# c64-stripefixvidbuf_v0_21-maxIC.net
KiCad netlist of a schematic drawn in EAGLE
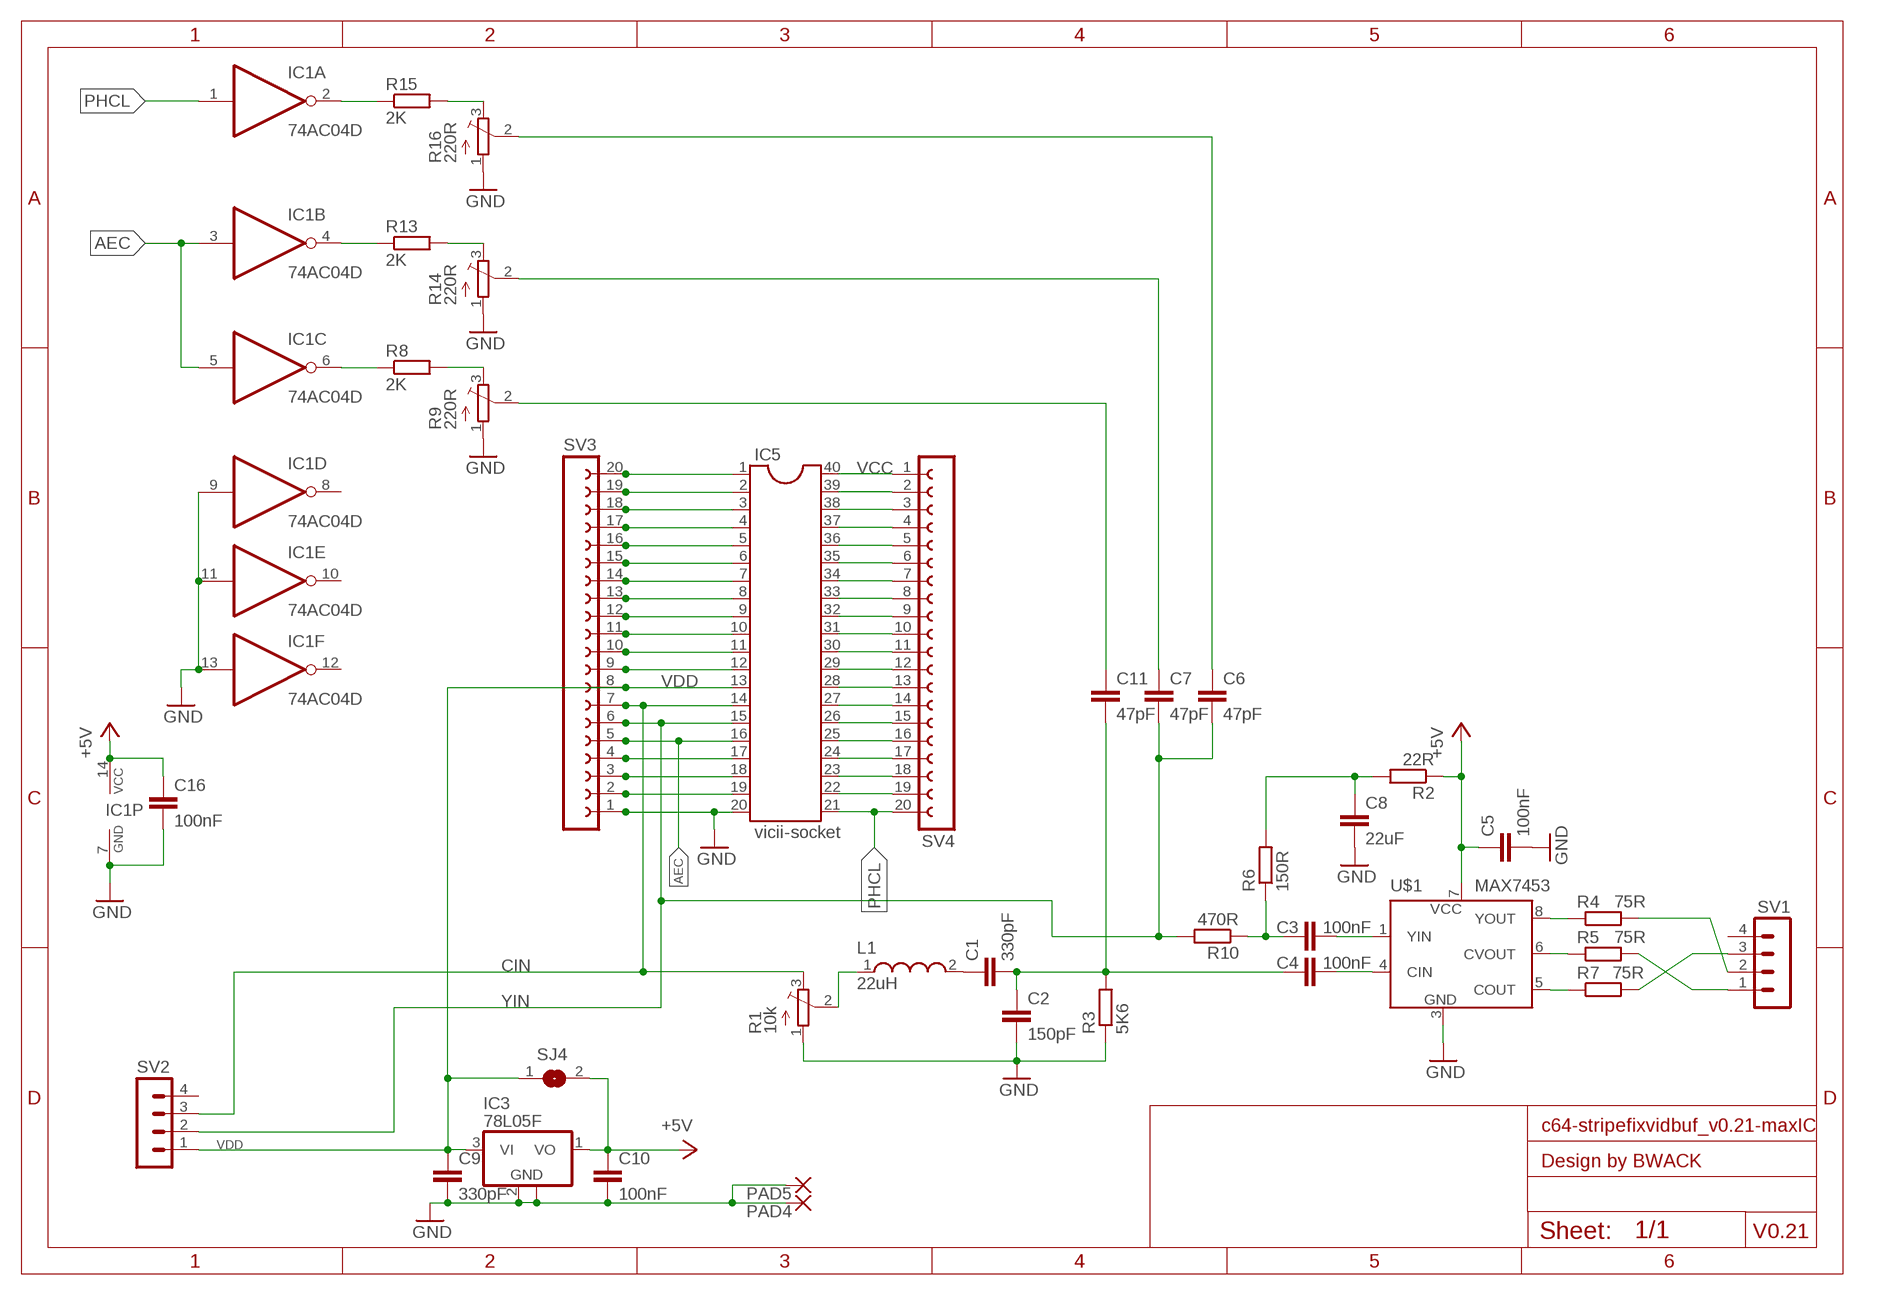
[diagram p0: schematic, sheet 1]

(export (version "E")
  (design (tool "Eeschema 10.0.6"))
  (components
    (comp (ref "C1")
      (value "330pF")
      (footprint "eagle-import:C0603")
      (libsource (lib "eagle-import") (part "C-EUC0603"))
    )
    (comp (ref "C2")
      (value "150pF")
      (footprint "eagle-import:C0603")
      (libsource (lib "eagle-import") (part "C-EUC0603"))
    )
    (comp (ref "C3")
      (value "100nF")
      (footprint "eagle-import:C0603")
      (libsource (lib "eagle-import") (part "C-EUC0603"))
    )
    (comp (ref "C4")
      (value "100nF")
      (footprint "eagle-import:C0603")
      (libsource (lib "eagle-import") (part "C-EUC0603"))
    )
    (comp (ref "C5")
      (value "100nF")
      (footprint "eagle-import:C0603")
      (libsource (lib "eagle-import") (part "C-EUC0603"))
    )
    (comp (ref "C6")
      (value "47pF")
      (footprint "eagle-import:C0603")
      (libsource (lib "eagle-import") (part "C-EUC0603"))
    )
    (comp (ref "C7")
      (value "47pF")
      (footprint "eagle-import:C0603")
      (libsource (lib "eagle-import") (part "C-EUC0603"))
    )
    (comp (ref "C8")
      (value "22uF")
      (footprint "eagle-import:C1206K")
      (libsource (lib "eagle-import") (part "C-EUC1206K"))
    )
    (comp (ref "C9")
      (value "330pF")
      (footprint "eagle-import:C0603")
      (libsource (lib "eagle-import") (part "C-EUC0603"))
    )
    (comp (ref "C10")
      (value "100nF")
      (footprint "eagle-import:C0603")
      (libsource (lib "eagle-import") (part "C-EUC0603"))
    )
    (comp (ref "C11")
      (value "47pF")
      (footprint "eagle-import:C0603")
      (libsource (lib "eagle-import") (part "C-EUC0603"))
    )
    (comp (ref "C16")
      (value "100nF")
      (footprint "eagle-import:C0603")
      (libsource (lib "eagle-import") (part "C-EUC0603"))
    )
    (comp (ref "IC1")
      (value "74AC04D")
      (footprint "eagle-import:SO14")
      (libsource (lib "eagle-import") (part "7404DAC"))
    )
    (comp (ref "IC3")
      (value "78L05F")
      (footprint "eagle-import:SOT89")
      (libsource (lib "eagle-import") (part "78LF05"))
    )
    (comp (ref "IC5")
      (value "vicii-socket")
      (footprint "eagle-import:DIL40SPECIAL")
      (libsource (lib "eagle-import") (part "DIL40SPECIAL"))
    )
    (comp (ref "L1")
      (value "22uH")
      (footprint "eagle-import:WE-KI_0805_B")
      (libsource (lib "eagle-import") (part "WE-KIHQ_0805"))
    )
    (comp (ref "PAD4")
      (value "2,15/1,0")
      (footprint "eagle-import:2,15_1,0")
      (libsource (lib "eagle-import") (part "2,15/1,0"))
    )
    (comp (ref "PAD5")
      (value "2,15/1,0")
      (footprint "eagle-import:2,15_1,0")
      (libsource (lib "eagle-import") (part "2,15/1,0"))
    )
    (comp (ref "R1")
      (value "10k")
      (footprint "eagle-import:TC33")
      (libsource (lib "eagle-import") (part "TRIM_EU-TC33"))
    )
    (comp (ref "R2")
      (value "22R")
      (footprint "eagle-import:R0603")
      (libsource (lib "eagle-import") (part "R-EU_R0603"))
    )
    (comp (ref "R3")
      (value "5K6")
      (footprint "eagle-import:R0603")
      (libsource (lib "eagle-import") (part "R-EU_R0603"))
    )
    (comp (ref "R4")
      (value "75R")
      (footprint "eagle-import:R0603")
      (libsource (lib "eagle-import") (part "R-EU_R0603"))
    )
    (comp (ref "R5")
      (value "75R")
      (footprint "eagle-import:R0603")
      (libsource (lib "eagle-import") (part "R-EU_R0603"))
    )
    (comp (ref "R6")
      (value "150R")
      (footprint "eagle-import:R0603")
      (libsource (lib "eagle-import") (part "R-EU_R0603"))
    )
    (comp (ref "R7")
      (value "75R")
      (footprint "eagle-import:R0603")
      (libsource (lib "eagle-import") (part "R-EU_R0603"))
    )
    (comp (ref "R8")
      (value "2K")
      (footprint "eagle-import:R0603")
      (libsource (lib "eagle-import") (part "R-EU_R0603"))
    )
    (comp (ref "R9")
      (value "220R")
      (footprint "eagle-import:TC33")
      (libsource (lib "eagle-import") (part "TRIM_EU-TC33"))
    )
    (comp (ref "R10")
      (value "470R")
      (footprint "eagle-import:R0603")
      (libsource (lib "eagle-import") (part "R-EU_R0603"))
    )
    (comp (ref "R13")
      (value "2K")
      (footprint "eagle-import:R0603")
      (libsource (lib "eagle-import") (part "R-EU_R0603"))
    )
    (comp (ref "R14")
      (value "220R")
      (footprint "eagle-import:TC33")
      (libsource (lib "eagle-import") (part "TRIM_EU-TC33"))
    )
    (comp (ref "R15")
      (value "2K")
      (footprint "eagle-import:R0603")
      (libsource (lib "eagle-import") (part "R-EU_R0603"))
    )
    (comp (ref "R16")
      (value "220R")
      (footprint "eagle-import:TC33")
      (libsource (lib "eagle-import") (part "TRIM_EU-TC33"))
    )
    (comp (ref "SJ4") (value "SJ") (footprint "eagle-import:SJ") (libsource (lib "eagle-import") (part "SJ")))
    (comp (ref "SV1")
      (value "MA04-1S")
      (footprint "eagle-import:MA04-1S")
      (libsource (lib "eagle-import") (part "MA04-1S"))
    )
    (comp (ref "SV2")
      (value "MA04-1S")
      (footprint "eagle-import:MA04-1S")
      (libsource (lib "eagle-import") (part "MA04-1S"))
    )
    (comp (ref "SV3")
      (value "FE20-1")
      (footprint "eagle-import:FE20")
      (libsource (lib "eagle-import") (part "FE20-1"))
    )
    (comp (ref "SV4")
      (value "FE20-1")
      (footprint "eagle-import:FE20")
      (fields (field (name "OC_FARNELL") "unknown") (field (name "OC_NEWARK") "unknown"))
      (libsource (lib "eagle-import") (part "FE20-1"))
    )
    (comp (ref "U$1")
      (value "MAX7453")
      (footprint "eagle-import:SO08")
      (libsource (lib "eagle-import") (part "MAX7453"))
    )
  )
  (nets
    (net (code "1") (name "+5V") (class "Default")
      (node (ref "C10") (pin "1") (pinfunction "1_1") (pintype "passive"))
      (node (ref "C16") (pin "1") (pinfunction "1_1") (pintype "passive"))
      (node (ref "C5") (pin "1") (pinfunction "1_1") (pintype "passive"))
      (node (ref "IC1") (pin "14") (pinfunction "VCC_14") (pintype "power_in"))
      (node (ref "IC3") (pin "1") (pinfunction "VO_1") (pintype "passive"))
      (node (ref "R2") (pin "1") (pinfunction "1_1") (pintype "passive"))
      (node (ref "SJ4") (pin "2") (pinfunction "2_2") (pintype "passive"))
      (node (ref "U$1") (pin "7") (pinfunction "V+_7") (pintype "power_in"))
    )
    (net (code "2") (name "/CIN") (class "Default")
      (node (ref "IC5") (pin "14") (pinfunction "14_14") (pintype "passive"))
      (node (ref "R1") (pin "3") (pinfunction "E_3") (pintype "passive"))
      (node (ref "SV2") (pin "3") (pinfunction "3_3") (pintype "passive"))
      (node (ref "SV3") (pin "7") (pinfunction "7_7") (pintype "passive"))
    )
    (net (code "3") (name "/VCC") (class "Default")
      (node (ref "IC5") (pin "40") (pinfunction "40_40") (pintype "passive"))
      (node (ref "SV4") (pin "1") (pinfunction "1_1") (pintype "passive"))
    )
    (net (code "4") (name "/VDD") (class "Default")
      (node (ref "C9") (pin "1") (pinfunction "1_1") (pintype "passive"))
      (node (ref "IC3") (pin "3") (pinfunction "VI_3") (pintype "input"))
      (node (ref "IC5") (pin "13") (pinfunction "13_13") (pintype "passive"))
      (node (ref "SJ4") (pin "1") (pinfunction "1_1") (pintype "passive"))
      (node (ref "SV2") (pin "1") (pinfunction "1_1") (pintype "passive"))
      (node (ref "SV3") (pin "8") (pinfunction "8_8") (pintype "passive"))
    )
    (net (code "5") (name "/YIN") (class "Default")
      (node (ref "C6") (pin "2") (pinfunction "2_2") (pintype "passive"))
      (node (ref "C7") (pin "2") (pinfunction "2_2") (pintype "passive"))
      (node (ref "IC5") (pin "15") (pinfunction "15_15") (pintype "passive"))
      (node (ref "R10") (pin "2") (pinfunction "2_2") (pintype "passive"))
      (node (ref "SV2") (pin "2") (pinfunction "2_2") (pintype "passive"))
      (node (ref "SV3") (pin "6") (pinfunction "6_6") (pintype "passive"))
    )
    (net (code "6") (name "AEC") (class "Default")
      (node (ref "IC1") (pin "3") (pinfunction "I_3") (pintype "input"))
      (node (ref "IC1") (pin "5") (pinfunction "I_5") (pintype "input"))
      (node (ref "IC5") (pin "16") (pinfunction "16_16") (pintype "passive"))
      (node (ref "SV3") (pin "5") (pinfunction "5_5") (pintype "passive"))
    )
    (net (code "7") (name "GND") (class "Default")
      (node (ref "C10") (pin "2") (pinfunction "2_2") (pintype "passive"))
      (node (ref "C16") (pin "2") (pinfunction "2_2") (pintype "passive"))
      (node (ref "C2") (pin "2") (pinfunction "2_2") (pintype "passive"))
      (node (ref "C5") (pin "2") (pinfunction "2_2") (pintype "passive"))
      (node (ref "C8") (pin "2") (pinfunction "2_2") (pintype "passive"))
      (node (ref "C9") (pin "2") (pinfunction "2_2") (pintype "passive"))
      (node (ref "IC1") (pin "11") (pinfunction "I_11") (pintype "input"))
      (node (ref "IC1") (pin "13") (pinfunction "I_13") (pintype "input"))
      (node (ref "IC1") (pin "7") (pinfunction "GND_7") (pintype "power_in"))
      (node (ref "IC1") (pin "9") (pinfunction "I_9") (pintype "input"))
      (node (ref "IC3") (pin "2") (pinfunction "GND_2") (pintype "passive"))
      (node (ref "IC3") (pin "2@1") (pinfunction "GND_2@1") (pintype "passive"))
      (node (ref "IC5") (pin "20") (pinfunction "20_20") (pintype "passive"))
      (node (ref "PAD4") (pin "1") (pinfunction "P_1") (pintype "passive"))
      (node (ref "PAD5") (pin "1") (pinfunction "P_1") (pintype "passive"))
      (node (ref "R1") (pin "1") (pinfunction "A_1") (pintype "passive"))
      (node (ref "R14") (pin "1") (pinfunction "A_1") (pintype "passive"))
      (node (ref "R16") (pin "1") (pinfunction "A_1") (pintype "passive"))
      (node (ref "R3") (pin "1") (pinfunction "1_1") (pintype "passive"))
      (node (ref "R9") (pin "1") (pinfunction "A_1") (pintype "passive"))
      (node (ref "SV3") (pin "1") (pinfunction "1_1") (pintype "passive"))
      (node (ref "U$1") (pin "3") (pinfunction "V-_3") (pintype "power_in"))
    )
    (net (code "8") (name "Net-(C1-Pad1)") (class "Default")
      (node (ref "C1") (pin "1") (pinfunction "1_1") (pintype "passive"))
      (node (ref "L1") (pin "2") (pinfunction "2_2") (pintype "passive"))
    )
    (net (code "9") (name "Net-(C1-Pad2)") (class "Default")
      (node (ref "C1") (pin "2") (pinfunction "2_2") (pintype "passive"))
      (node (ref "C11") (pin "2") (pinfunction "2_2") (pintype "passive"))
      (node (ref "C2") (pin "1") (pinfunction "1_1") (pintype "passive"))
      (node (ref "C4") (pin "1") (pinfunction "1_1") (pintype "passive"))
      (node (ref "R3") (pin "2") (pinfunction "2_2") (pintype "passive"))
    )
    (net (code "10") (name "Net-(C3-Pad1)") (class "Default")
      (node (ref "C3") (pin "1") (pinfunction "1_1") (pintype "passive"))
      (node (ref "R10") (pin "1") (pinfunction "1_1") (pintype "passive"))
      (node (ref "R6") (pin "1") (pinfunction "1_1") (pintype "passive"))
    )
    (net (code "11") (name "Net-(C8-Pad1)") (class "Default")
      (node (ref "C8") (pin "1") (pinfunction "1_1") (pintype "passive"))
      (node (ref "R2") (pin "2") (pinfunction "2_2") (pintype "passive"))
      (node (ref "R6") (pin "2") (pinfunction "2_2") (pintype "passive"))
    )
    (net (code "12") (name "Net-(IC1A-O)") (class "Default")
      (node (ref "IC1") (pin "2") (pinfunction "O_2") (pintype "output"))
      (node (ref "R15") (pin "1") (pinfunction "1_1") (pintype "passive"))
    )
    (net (code "13") (name "Net-(IC1B-O)") (class "Default")
      (node (ref "IC1") (pin "4") (pinfunction "O_4") (pintype "output"))
      (node (ref "R13") (pin "1") (pinfunction "1_1") (pintype "passive"))
    )
    (net (code "14") (name "Net-(IC1C-O)") (class "Default")
      (node (ref "IC1") (pin "6") (pinfunction "O_6") (pintype "output"))
      (node (ref "R8") (pin "1") (pinfunction "1_1") (pintype "passive"))
    )
    (net (code "15") (name "Net-(IC5-Pad1)") (class "Default")
      (node (ref "IC5") (pin "1") (pinfunction "1_1") (pintype "passive"))
      (node (ref "SV3") (pin "20") (pinfunction "20_20") (pintype "passive"))
    )
    (net (code "16") (name "Net-(IC5-Pad2)") (class "Default")
      (node (ref "IC5") (pin "2") (pinfunction "2_2") (pintype "passive"))
      (node (ref "SV3") (pin "19") (pinfunction "19_19") (pintype "passive"))
    )
    (net (code "17") (name "Net-(IC5-Pad3)") (class "Default")
      (node (ref "IC5") (pin "3") (pinfunction "3_3") (pintype "passive"))
      (node (ref "SV3") (pin "18") (pinfunction "18_18") (pintype "passive"))
    )
    (net (code "18") (name "Net-(IC5-Pad4)") (class "Default")
      (node (ref "IC5") (pin "4") (pinfunction "4_4") (pintype "passive"))
      (node (ref "SV3") (pin "17") (pinfunction "17_17") (pintype "passive"))
    )
    (net (code "19") (name "Net-(IC5-Pad5)") (class "Default")
      (node (ref "IC5") (pin "5") (pinfunction "5_5") (pintype "passive"))
      (node (ref "SV3") (pin "16") (pinfunction "16_16") (pintype "passive"))
    )
    (net (code "20") (name "Net-(IC5-Pad6)") (class "Default")
      (node (ref "IC5") (pin "6") (pinfunction "6_6") (pintype "passive"))
      (node (ref "SV3") (pin "15") (pinfunction "15_15") (pintype "passive"))
    )
    (net (code "21") (name "Net-(IC5-Pad7)") (class "Default")
      (node (ref "IC5") (pin "7") (pinfunction "7_7") (pintype "passive"))
      (node (ref "SV3") (pin "14") (pinfunction "14_14") (pintype "passive"))
    )
    (net (code "22") (name "Net-(IC5-Pad8)") (class "Default")
      (node (ref "IC5") (pin "8") (pinfunction "8_8") (pintype "passive"))
      (node (ref "SV3") (pin "13") (pinfunction "13_13") (pintype "passive"))
    )
    (net (code "23") (name "Net-(IC5-Pad9)") (class "Default")
      (node (ref "IC5") (pin "9") (pinfunction "9_9") (pintype "passive"))
      (node (ref "SV3") (pin "12") (pinfunction "12_12") (pintype "passive"))
    )
    (net (code "24") (name "Net-(IC5-Pad10)") (class "Default")
      (node (ref "IC5") (pin "10") (pinfunction "10_10") (pintype "passive"))
      (node (ref "SV3") (pin "11") (pinfunction "11_11") (pintype "passive"))
    )
    (net (code "25") (name "Net-(IC5-Pad11)") (class "Default")
      (node (ref "IC5") (pin "11") (pinfunction "11_11") (pintype "passive"))
      (node (ref "SV3") (pin "10") (pinfunction "10_10") (pintype "passive"))
    )
    (net (code "26") (name "Net-(IC5-Pad12)") (class "Default")
      (node (ref "IC5") (pin "12") (pinfunction "12_12") (pintype "passive"))
      (node (ref "SV3") (pin "9") (pinfunction "9_9") (pintype "passive"))
    )
    (net (code "27") (name "Net-(IC5-Pad17)") (class "Default")
      (node (ref "IC5") (pin "17") (pinfunction "17_17") (pintype "passive"))
      (node (ref "SV3") (pin "4") (pinfunction "4_4") (pintype "passive"))
    )
    (net (code "28") (name "Net-(IC5-Pad18)") (class "Default")
      (node (ref "IC5") (pin "18") (pinfunction "18_18") (pintype "passive"))
      (node (ref "SV3") (pin "3") (pinfunction "3_3") (pintype "passive"))
    )
    (net (code "29") (name "Net-(IC5-Pad19)") (class "Default")
      (node (ref "IC5") (pin "19") (pinfunction "19_19") (pintype "passive"))
      (node (ref "SV3") (pin "2") (pinfunction "2_2") (pintype "passive"))
    )
    (net (code "30") (name "Net-(IC5-Pad22)") (class "Default")
      (node (ref "IC5") (pin "22") (pinfunction "22_22") (pintype "passive"))
      (node (ref "SV4") (pin "19") (pinfunction "19_19") (pintype "passive"))
    )
    (net (code "31") (name "Net-(IC5-Pad23)") (class "Default")
      (node (ref "IC5") (pin "23") (pinfunction "23_23") (pintype "passive"))
      (node (ref "SV4") (pin "18") (pinfunction "18_18") (pintype "passive"))
    )
    (net (code "32") (name "Net-(IC5-Pad24)") (class "Default")
      (node (ref "IC5") (pin "24") (pinfunction "24_24") (pintype "passive"))
      (node (ref "SV4") (pin "17") (pinfunction "17_17") (pintype "passive"))
    )
    (net (code "33") (name "Net-(IC5-Pad25)") (class "Default")
      (node (ref "IC5") (pin "25") (pinfunction "25_25") (pintype "passive"))
      (node (ref "SV4") (pin "16") (pinfunction "16_16") (pintype "passive"))
    )
    (net (code "34") (name "Net-(IC5-Pad26)") (class "Default")
      (node (ref "IC5") (pin "26") (pinfunction "26_26") (pintype "passive"))
      (node (ref "SV4") (pin "15") (pinfunction "15_15") (pintype "passive"))
    )
    (net (code "35") (name "Net-(IC5-Pad27)") (class "Default")
      (node (ref "IC5") (pin "27") (pinfunction "27_27") (pintype "passive"))
      (node (ref "SV4") (pin "14") (pinfunction "14_14") (pintype "passive"))
    )
    (net (code "36") (name "Net-(IC5-Pad28)") (class "Default")
      (node (ref "IC5") (pin "28") (pinfunction "28_28") (pintype "passive"))
      (node (ref "SV4") (pin "13") (pinfunction "13_13") (pintype "passive"))
    )
    (net (code "37") (name "Net-(IC5-Pad29)") (class "Default")
      (node (ref "IC5") (pin "29") (pinfunction "29_29") (pintype "passive"))
      (node (ref "SV4") (pin "12") (pinfunction "12_12") (pintype "passive"))
    )
    (net (code "38") (name "Net-(IC5-Pad30)") (class "Default")
      (node (ref "IC5") (pin "30") (pinfunction "30_30") (pintype "passive"))
      (node (ref "SV4") (pin "11") (pinfunction "11_11") (pintype "passive"))
    )
    (net (code "39") (name "Net-(IC5-Pad31)") (class "Default")
      (node (ref "IC5") (pin "31") (pinfunction "31_31") (pintype "passive"))
      (node (ref "SV4") (pin "10") (pinfunction "10_10") (pintype "passive"))
    )
    (net (code "40") (name "Net-(IC5-Pad32)") (class "Default")
      (node (ref "IC5") (pin "32") (pinfunction "32_32") (pintype "passive"))
      (node (ref "SV4") (pin "9") (pinfunction "9_9") (pintype "passive"))
    )
    (net (code "41") (name "Net-(IC5-Pad33)") (class "Default")
      (node (ref "IC5") (pin "33") (pinfunction "33_33") (pintype "passive"))
      (node (ref "SV4") (pin "8") (pinfunction "8_8") (pintype "passive"))
    )
    (net (code "42") (name "Net-(IC5-Pad34)") (class "Default")
      (node (ref "IC5") (pin "34") (pinfunction "34_34") (pintype "passive"))
      (node (ref "SV4") (pin "7") (pinfunction "7_7") (pintype "passive"))
    )
    (net (code "43") (name "Net-(IC5-Pad35)") (class "Default")
      (node (ref "IC5") (pin "35") (pinfunction "35_35") (pintype "passive"))
      (node (ref "SV4") (pin "6") (pinfunction "6_6") (pintype "passive"))
    )
    (net (code "44") (name "Net-(IC5-Pad36)") (class "Default")
      (node (ref "IC5") (pin "36") (pinfunction "36_36") (pintype "passive"))
      (node (ref "SV4") (pin "5") (pinfunction "5_5") (pintype "passive"))
    )
    (net (code "45") (name "Net-(IC5-Pad37)") (class "Default")
      (node (ref "IC5") (pin "37") (pinfunction "37_37") (pintype "passive"))
      (node (ref "SV4") (pin "4") (pinfunction "4_4") (pintype "passive"))
    )
    (net (code "46") (name "Net-(IC5-Pad38)") (class "Default")
      (node (ref "IC5") (pin "38") (pinfunction "38_38") (pintype "passive"))
      (node (ref "SV4") (pin "3") (pinfunction "3_3") (pintype "passive"))
    )
    (net (code "47") (name "Net-(IC5-Pad39)") (class "Default")
      (node (ref "IC5") (pin "39") (pinfunction "39_39") (pintype "passive"))
      (node (ref "SV4") (pin "2") (pinfunction "2_2") (pintype "passive"))
    )
    (net (code "48") (name "Net-(R1-S)") (class "Default")
      (node (ref "L1") (pin "1") (pinfunction "1_1") (pintype "passive"))
      (node (ref "R1") (pin "2") (pinfunction "S_2") (pintype "passive"))
    )
    (net (code "49") (name "Net-(R4-Pad2)") (class "Default")
      (node (ref "R4") (pin "2") (pinfunction "2_2") (pintype "passive"))
      (node (ref "SV1") (pin "2") (pinfunction "2_2") (pintype "passive"))
    )
    (net (code "50") (name "Net-(R5-Pad2)") (class "Default")
      (node (ref "R5") (pin "2") (pinfunction "2_2") (pintype "passive"))
      (node (ref "SV1") (pin "1") (pinfunction "1_1") (pintype "passive"))
    )
    (net (code "51") (name "Net-(R7-Pad2)") (class "Default")
      (node (ref "R7") (pin "2") (pinfunction "2_2") (pintype "passive"))
      (node (ref "SV1") (pin "3") (pinfunction "3_3") (pintype "passive"))
    )
    (net (code "52") (name "Net-(R9-E)") (class "Default")
      (node (ref "R8") (pin "2") (pinfunction "2_2") (pintype "passive"))
      (node (ref "R9") (pin "3") (pinfunction "E_3") (pintype "passive"))
    )
    (net (code "53") (name "Net-(R9-S)") (class "Default")
      (node (ref "C11") (pin "1") (pinfunction "1_1") (pintype "passive"))
      (node (ref "R9") (pin "2") (pinfunction "S_2") (pintype "passive"))
    )
    (net (code "54") (name "Net-(R14-E)") (class "Default")
      (node (ref "R13") (pin "2") (pinfunction "2_2") (pintype "passive"))
      (node (ref "R14") (pin "3") (pinfunction "E_3") (pintype "passive"))
    )
    (net (code "55") (name "Net-(R14-S)") (class "Default")
      (node (ref "C7") (pin "1") (pinfunction "1_1") (pintype "passive"))
      (node (ref "R14") (pin "2") (pinfunction "S_2") (pintype "passive"))
    )
    (net (code "56") (name "Net-(R16-E)") (class "Default")
      (node (ref "R15") (pin "2") (pinfunction "2_2") (pintype "passive"))
      (node (ref "R16") (pin "3") (pinfunction "E_3") (pintype "passive"))
    )
    (net (code "57") (name "Net-(R16-S)") (class "Default")
      (node (ref "C6") (pin "1") (pinfunction "1_1") (pintype "passive"))
      (node (ref "R16") (pin "2") (pinfunction "S_2") (pintype "passive"))
    )
    (net (code "58") (name "Net-(U$1-CIN)") (class "Default")
      (node (ref "C4") (pin "2") (pinfunction "2_2") (pintype "passive"))
      (node (ref "U$1") (pin "4") (pinfunction "CIN_4") (pintype "input"))
    )
    (net (code "59") (name "Net-(U$1-COUT)") (class "Default")
      (node (ref "R7") (pin "1") (pinfunction "1_1") (pintype "passive"))
      (node (ref "U$1") (pin "5") (pinfunction "COUT_5") (pintype "output"))
    )
    (net (code "60") (name "Net-(U$1-CVOUT)") (class "Default")
      (node (ref "R5") (pin "1") (pinfunction "1_1") (pintype "passive"))
      (node (ref "U$1") (pin "6") (pinfunction "CVOUT_6") (pintype "output"))
    )
    (net (code "61") (name "Net-(U$1-YIN)") (class "Default")
      (node (ref "C3") (pin "2") (pinfunction "2_2") (pintype "passive"))
      (node (ref "U$1") (pin "1") (pinfunction "YIN_1") (pintype "input"))
    )
    (net (code "62") (name "Net-(U$1-YOUT)") (class "Default")
      (node (ref "R4") (pin "1") (pinfunction "1_1") (pintype "passive"))
      (node (ref "U$1") (pin "8") (pinfunction "YOUT_8") (pintype "output"))
    )
    (net (code "63") (name "PHCL") (class "Default")
      (node (ref "IC1") (pin "1") (pinfunction "I_1") (pintype "input"))
      (node (ref "IC5") (pin "21") (pinfunction "21_21") (pintype "passive"))
      (node (ref "SV4") (pin "20") (pinfunction "20_20") (pintype "passive"))
    )
    (net (code "64") (name "unconnected-(IC1D-O-Pad8)") (class "Default")
      (node (ref "IC1") (pin "8") (pinfunction "O_8") (pintype "output"))
    )
    (net (code "65") (name "unconnected-(IC1E-O-Pad10)") (class "Default")
      (node (ref "IC1") (pin "10") (pinfunction "O_10") (pintype "output"))
    )
    (net (code "66") (name "unconnected-(IC1F-O-Pad12)") (class "Default")
      (node (ref "IC1") (pin "12") (pinfunction "O_12") (pintype "output"))
    )
    (net (code "67") (name "unconnected-(SV1-Pad4)") (class "Default")
      (node (ref "SV1") (pin "4") (pinfunction "4_4") (pintype "passive"))
    )
    (net (code "68") (name "unconnected-(SV2-Pad4)") (class "Default")
      (node (ref "SV2") (pin "4") (pinfunction "4_4") (pintype "passive"))
    )
  )
)
